# LNA.net
KiCad netlist of a schematic drawn in Altium Designer
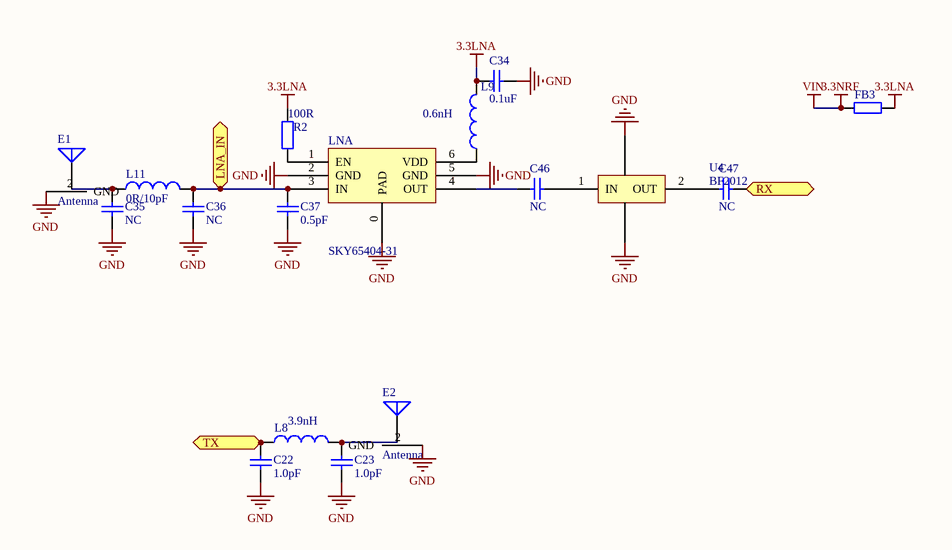
[diagram p0: LNA.SchDoc]

(export (version "E")
  (design (tool "Eeschema 10.0.6"))
  (components
    (comp (ref "C22")
      (value "1.0pF")
      (footprint "0402")
      (description "Capacitor")
      (fields (field (name "Comment") "Cap") (field (name "PUBLISHER") "Altium Limited"))
      (libsource (lib "RTC6705") (part "Cap"))
    )
    (comp (ref "C23")
      (value "1.0pF")
      (footprint "0402")
      (description "Capacitor")
      (fields (field (name "Comment") "Cap") (field (name "PUBLISHER") "Altium Limited"))
      (libsource (lib "RTC6705") (part "Cap"))
    )
    (comp (ref "C34")
      (value "0.1uF")
      (footprint "0402")
      (description "Capacitor")
      (fields (field (name "Comment") "Cap") (field (name "PUBLISHER") "Altium Limited"))
      (libsource (lib "RTC6705") (part "Cap"))
    )
    (comp (ref "C35")
      (value "NC")
      (footprint "0402")
      (description "Capacitor")
      (fields (field (name "Comment") "Cap") (field (name "PUBLISHER") "Altium Limited"))
      (libsource (lib "RTC6705") (part "Cap"))
    )
    (comp (ref "C36")
      (value "NC")
      (footprint "0402")
      (description "Capacitor")
      (fields (field (name "Comment") "Cap") (field (name "PUBLISHER") "Altium Limited"))
      (libsource (lib "RTC6705") (part "Cap"))
    )
    (comp (ref "C37")
      (value "0.5pF")
      (footprint "0402")
      (description "Capacitor")
      (fields (field (name "Comment") "Cap") (field (name "PUBLISHER") "Altium Limited"))
      (libsource (lib "RTC6705") (part "Cap"))
    )
    (comp (ref "C46")
      (value "NC")
      (footprint "0402")
      (description "Capacitor")
      (fields (field (name "Comment") "Cap") (field (name "PUBLISHER") "Altium Limited"))
      (libsource (lib "RTC6705") (part "Cap"))
    )
    (comp (ref "C47")
      (value "NC")
      (footprint "0402")
      (description "Capacitor")
      (fields (field (name "Comment") "Cap") (field (name "PUBLISHER") "Altium Limited"))
      (libsource (lib "RTC6705") (part "Cap"))
    )
    (comp (ref "E1")
      (value "Antenna")
      (footprint "IPEX")
      (description "Generic Antenna")
      (fields (field (name "PUBLISHER") "Altium Limited"))
      (libsource (lib "Miscellaneous Devices") (part "Antenna"))
    )
    (comp (ref "E2")
      (value "Antenna")
      (footprint "IPEX")
      (description "Generic Antenna")
      (fields (field (name "PUBLISHER") "Altium Limited"))
      (libsource (lib "Miscellaneous Devices") (part "Antenna"))
    )
    (comp (ref "FB3")
      (value "Res2")
      (footprint "0402")
      (description "Resistor")
      (fields (field (name "PUBLISHER") "Altium Limited"))
      (libsource (lib "") (part "Res2_1"))
    )
    (comp (ref "L8")
      (value "3.9nH")
      (footprint "0402")
      (description "Inductor")
      (fields (field (name "PUBLISHER") "Altium Limited"))
      (libsource (lib "Miscellaneous Devices") (part "Inductor"))
    )
    (comp (ref "L9")
      (value "0.6nH")
      (footprint "0402")
      (description "Inductor")
      (fields (field (name "PUBLISHER") "Altium Limited"))
      (libsource (lib "Miscellaneous Devices") (part "Inductor"))
    )
    (comp (ref "L11")
      (value "0R/10pF")
      (footprint "0402")
      (description "Inductor")
      (fields (field (name "PUBLISHER") "Altium Limited"))
      (libsource (lib "Miscellaneous Devices") (part "Inductor"))
    )
    (comp (ref "LNA")
      (value "SKY65404-31")
      (footprint "SKY65404-31")
      (libsource (lib "BK5811") (part "SKY65404-31"))
    )
    (comp (ref "R2")
      (value "100R")
      (footprint "0402")
      (description "Resistor")
      (fields (field (name "Comment") "Res2") (field (name "PUBLISHER") "Altium Limited"))
      (libsource (lib "RTC6705") (part "Res2"))
    )
    (comp (ref "U4") (value "BF2012") (footprint "LFB2H5") (libsource (lib "RTC6705") (part "BF2012")))
  )
  (nets
    (net (code "1") (name "/LNA_IN") (class "Default")
      (node (ref "C36") (pin "2") (pinfunction "2_2") (pintype "passive"))
      (node (ref "C37") (pin "2") (pinfunction "2_2") (pintype "passive"))
      (node (ref "L11") (pin "2") (pinfunction "2_2") (pintype "passive"))
      (node (ref "LNA") (pin "3") (pinfunction "IN_3") (pintype "passive"))
    )
    (net (code "2") (name "/RX") (class "Default")
      (node (ref "C47") (pin "2") (pinfunction "2_2") (pintype "passive"))
    )
    (net (code "3") (name "/TX") (class "Default")
      (node (ref "C22") (pin "1") (pinfunction "1_1") (pintype "passive"))
      (node (ref "L8") (pin "1") (pinfunction "1_1") (pintype "passive"))
    )
    (net (code "4") (name "3.3LNA") (class "Default")
      (node (ref "C34") (pin "2") (pinfunction "2_2") (pintype "passive"))
      (node (ref "FB3") (pin "2") (pinfunction "2_2") (pintype "passive"))
      (node (ref "L9") (pin "2") (pinfunction "2_2") (pintype "passive"))
      (node (ref "R2") (pin "2") (pinfunction "2_2") (pintype "passive"))
    )
    (net (code "5") (name "3.3NRF") (class "Default")
      (node (ref "FB3") (pin "1") (pinfunction "1_1") (pintype "passive"))
    )
    (net (code "6") (name "GND") (class "Default")
      (node (ref "C22") (pin "2") (pinfunction "2_2") (pintype "passive"))
      (node (ref "C23") (pin "2") (pinfunction "2_2") (pintype "passive"))
      (node (ref "C34") (pin "1") (pinfunction "1_1") (pintype "passive"))
      (node (ref "C35") (pin "1") (pinfunction "1_1") (pintype "passive"))
      (node (ref "C36") (pin "1") (pinfunction "1_1") (pintype "passive"))
      (node (ref "C37") (pin "1") (pinfunction "1_1") (pintype "passive"))
      (node (ref "E1") (pin "2") (pinfunction "GND_2") (pintype "passive"))
      (node (ref "E2") (pin "2") (pinfunction "GND_2") (pintype "passive"))
      (node (ref "LNA") (pin "0") (pinfunction "PAD_0") (pintype "passive"))
      (node (ref "LNA") (pin "2") (pinfunction "GND_2") (pintype "passive"))
      (node (ref "LNA") (pin "5") (pinfunction "GND_5") (pintype "passive"))
      (node (ref "U4") (pin "0") (pinfunction "GND_0") (pintype "passive"))
    )
    (net (code "7") (name "Net-(E1-ANT)") (class "Default")
      (node (ref "C35") (pin "2") (pinfunction "2_2") (pintype "passive"))
      (node (ref "E1") (pin "1") (pinfunction "ANT_1") (pintype "passive"))
      (node (ref "L11") (pin "1") (pinfunction "1_1") (pintype "passive"))
    )
    (net (code "8") (name "Net-(E2-ANT)") (class "Default")
      (node (ref "C23") (pin "1") (pinfunction "1_1") (pintype "passive"))
      (node (ref "E2") (pin "1") (pinfunction "ANT_1") (pintype "passive"))
      (node (ref "L8") (pin "2") (pinfunction "2_2") (pintype "passive"))
    )
    (net (code "9") (name "Net-(LNA-EN)") (class "Default")
      (node (ref "LNA") (pin "1") (pinfunction "EN_1") (pintype "passive"))
      (node (ref "R2") (pin "1") (pinfunction "1_1") (pintype "passive"))
    )
    (net (code "10") (name "Net-(LNA-OUT)") (class "Default")
      (node (ref "C46") (pin "1") (pinfunction "1_1") (pintype "passive"))
      (node (ref "LNA") (pin "4") (pinfunction "OUT_4") (pintype "passive"))
    )
    (net (code "11") (name "Net-(LNA-VDD)") (class "Default")
      (node (ref "L9") (pin "1") (pinfunction "1_1") (pintype "passive"))
      (node (ref "LNA") (pin "6") (pinfunction "VDD_6") (pintype "passive"))
    )
    (net (code "12") (name "Net-(U4-IN)") (class "Default")
      (node (ref "C46") (pin "2") (pinfunction "2_2") (pintype "passive"))
      (node (ref "U4") (pin "1") (pinfunction "IN_1") (pintype "passive"))
    )
    (net (code "13") (name "Net-(U4-OUT)") (class "Default")
      (node (ref "C47") (pin "1") (pinfunction "1_1") (pintype "passive"))
      (node (ref "U4") (pin "2") (pinfunction "OUT_2") (pintype "passive"))
    )
  )
)
